# finalproject.net
KiCad netlist of a schematic drawn in Altium Designer
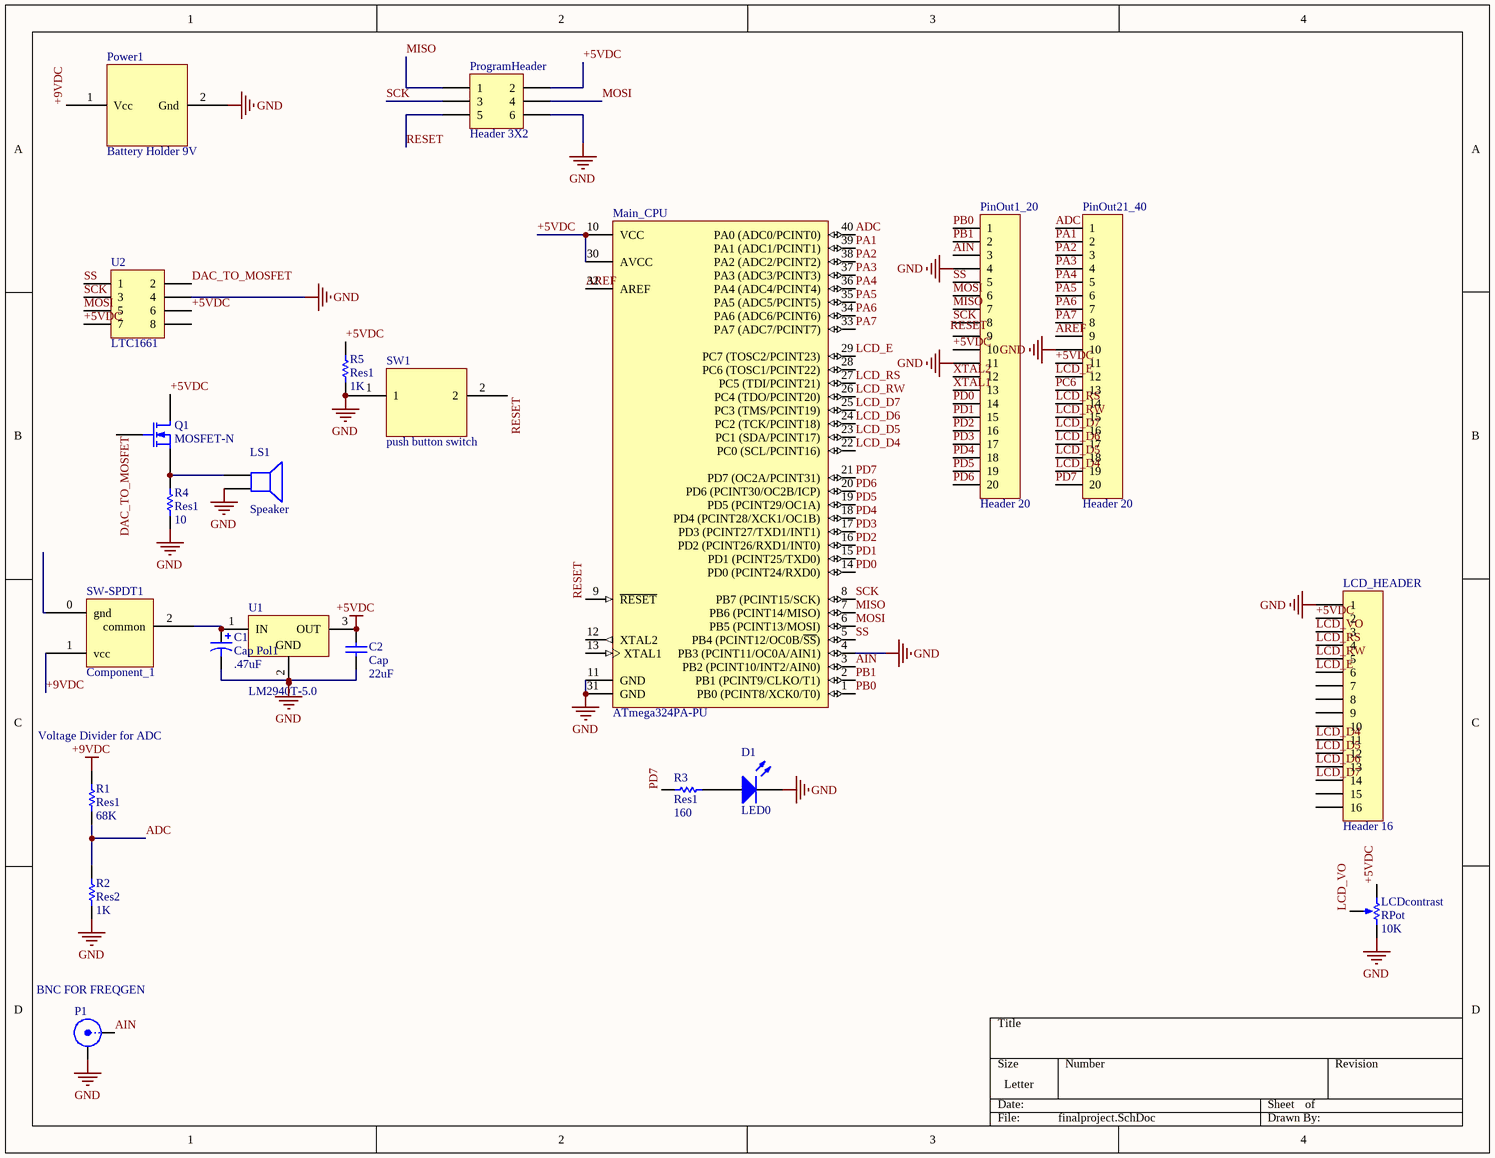
[diagram p0: finalproject.SchDoc]

(export (version "E")
  (design (tool "Eeschema 10.0.6"))
  (components
    (comp (ref "C1")
      (value "Cap Pol1")
      (footprint "HDR1X2")
      (description "Polarized Capacitor (Radial)")
      (fields (field (name "ALTIUM_VALUE") ".47uF") (field (name "PUBLISHER") "Altium Limited"))
      (libsource (lib "Miscellaneous Devices") (part "Cap Pol1"))
    )
    (comp (ref "C2")
      (value "Cap")
      (footprint "Vishay Sprague Tantalum Axial-Lead Capacitor:CSR13-D")
      (description "Capacitor")
      (fields (field (name "ALTIUM_VALUE") "22uF") (field (name "PUBLISHER") "Altium Limited"))
      (libsource (lib "Miscellaneous Devices") (part "Cap"))
    )
    (comp (ref "D1")
      (value "LED0")
      (footprint "HDR1X2")
      (description "Typical INFRARED GaAs LED")
      (fields (field (name "PUBLISHER") "Altium Limited"))
      (libsource (lib "Miscellaneous Devices") (part "LED0"))
    )
    (comp (ref "LCDcontrast")
      (value "RPot")
      (footprint "VR5")
      (description "Potentiometer")
      (fields (field (name "ALTIUM_VALUE") "10K") (field (name "PUBLISHER") "Altium Limited"))
      (libsource (lib "Miscellaneous Devices") (part "RPot"))
    )
    (comp (ref "LCD_HEADER")
      (value "Header 16")
      (footprint "HDR1X16")
      (description "Header, 16-Pin")
      (fields (field (name "PUBLISHER") "Altium Limited"))
      (libsource (lib "Miscellaneous Connectors") (part "Header 16"))
    )
    (comp (ref "LS1")
      (value "Speaker")
      (footprint "PIN2")
      (description "Loudspeaker")
      (fields (field (name "PUBLISHER") "Altium Limited"))
      (libsource (lib "Miscellaneous Devices") (part "Speaker"))
    )
    (comp (ref "Main_CPU")
      (value "ATmega324PA-PU")
      (footprint "40P6")
      (fields (field (name "PUBLISHER") "Altium Limited"))
      (libsource (lib "Atmel Microcontroller 8-Bit megaAVR") (part "ATmega324PA-PU"))
    )
    (comp (ref "P1")
      (value "BNC FOR FREQGEN")
      (footprint "BNC_RA CON")
      (description "BNC Elbow Connector")
      (fields (field (name "PUBLISHER") "Altium Limited"))
      (libsource (lib "Miscellaneous Connectors") (part "BNC"))
    )
    (comp (ref "PinOut1_20")
      (value "Header 20")
      (footprint "HDR1X20")
      (description "Header, 20-Pin")
      (fields (field (name "PUBLISHER") "Altium Limited"))
      (libsource (lib "Miscellaneous Connectors") (part "Header 20"))
    )
    (comp (ref "PinOut21_40")
      (value "Header 20")
      (footprint "HDR1X20")
      (description "Header, 20-Pin")
      (fields (field (name "PUBLISHER") "Altium Limited"))
      (libsource (lib "Miscellaneous Connectors") (part "Header 20"))
    )
    (comp (ref "Power1")
      (value "Battery Holder 9V")
      (footprint "PCBComponent_1 - duplicate")
      (libsource (lib "JDlibs") (part "Battery Holder 9V"))
    )
    (comp (ref "ProgramHeader")
      (value "Header 3X2")
      (footprint "HDR2X3")
      (description "Header, 3-Pin, Dual row")
      (fields (field (name "PUBLISHER") "Altium Limited"))
      (libsource (lib "Miscellaneous Connectors") (part "Header 3X2"))
    )
    (comp (ref "Q1")
      (value "MOSFET-N")
      (footprint "HDR1X3")
      (description "N-Channel MOSFET")
      (fields (field (name "PUBLISHER") "Altium Limited"))
      (libsource (lib "Miscellaneous Devices") (part "MOSFET-N"))
    )
    (comp (ref "R1")
      (value "Res1")
      (footprint "AXIAL-0.3")
      (description "Resistor")
      (fields (field (name "ALTIUM_VALUE") "68K") (field (name "PUBLISHER") "Altium Limited"))
      (libsource (lib "Miscellaneous Devices") (part "Res1"))
    )
    (comp (ref "R2")
      (value "Res2")
      (footprint "AXIAL-0.3")
      (description "Resistor")
      (fields (field (name "ALTIUM_VALUE") "1K") (field (name "PUBLISHER") "Altium Limited"))
      (libsource (lib "Miscellaneous Devices") (part "Res1"))
    )
    (comp (ref "R3")
      (value "Res1")
      (footprint "AXIAL-0.3")
      (description "Resistor")
      (fields (field (name "ALTIUM_VALUE") "160") (field (name "PUBLISHER") "Altium Limited"))
      (libsource (lib "Miscellaneous Devices") (part "Res1"))
    )
    (comp (ref "R4")
      (value "Res1")
      (footprint "AXIAL-0.3")
      (description "Resistor")
      (fields (field (name "ALTIUM_VALUE") "10") (field (name "PUBLISHER") "Altium Limited"))
      (libsource (lib "Miscellaneous Devices") (part "Res1"))
    )
    (comp (ref "R5")
      (value "Res1")
      (footprint "AXIAL-0.3")
      (description "Resistor")
      (fields (field (name "ALTIUM_VALUE") "1K") (field (name "PUBLISHER") "Altium Limited"))
      (libsource (lib "Miscellaneous Devices") (part "Res1"))
    )
    (comp (ref "SW-SPDT1")
      (value "Component_1")
      (footprint "PCBComponent_1")
      (libsource (lib "JDlibs") (part "Component_1"))
    )
    (comp (ref "SW1")
      (value "push button switch")
      (footprint "SW-PUSH-4")
      (libsource (lib "JDlibs") (part "SW-PUSH"))
    )
    (comp (ref "U1")
      (value "LM2940T-5.0")
      (footprint "T03B")
      (description "1A Low Dropout Regulator, 3-pin TO-220")
      (fields
        (field (name "MANUFACTURER") "National Semiconductor")
        (field (name "PUBLISHER") "Altium Limited")
      )
      (libsource (lib "NSC LDO") (part "LM2940T-5.0"))
    )
    (comp (ref "U2")
      (value "LTC1661")
      (footprint "DIP-8")
      (description "Header, 4-Pin, Dual row")
      (fields (field (name "PUBLISHER") "Altium Limited"))
      (libsource (lib "Miscellaneous Connectors") (part "Header 4X2"))
    )
  )
  (nets
    (net (code "1") (name "+5VDC") (class "Default")
      (node (ref "C2") (pin "2") (pinfunction "2_2") (pintype "passive"))
      (node (ref "LCD_HEADER") (pin "2") (pinfunction "2_2") (pintype "passive"))
      (node (ref "LCDcontrast") (pin "1") (pinfunction "TOP_1") (pintype "passive"))
      (node (ref "Main_CPU") (pin "10") (pinfunction "VCC_10") (pintype "power_in"))
      (node (ref "Main_CPU") (pin "30") (pinfunction "AVCC_30") (pintype "power_in"))
      (node (ref "PinOut1_20") (pin "10") (pinfunction "10_10") (pintype "passive"))
      (node (ref "PinOut21_40") (pin "11") (pinfunction "11_11") (pintype "passive"))
      (node (ref "ProgramHeader") (pin "2") (pinfunction "2_2") (pintype "passive"))
      (node (ref "Q1") (pin "1") (pinfunction "D_1") (pintype "passive"))
      (node (ref "R5") (pin "2") (pinfunction "2_2") (pintype "passive"))
      (node (ref "U1") (pin "3") (pinfunction "OUT_3") (pintype "power_in"))
      (node (ref "U2") (pin "6") (pinfunction "6_6") (pintype "passive"))
      (node (ref "U2") (pin "7") (pinfunction "7_7") (pintype "passive"))
    )
    (net (code "2") (name "+9VDC") (class "Default")
      (node (ref "Power1") (pin "1") (pinfunction "Vcc_1") (pintype "passive"))
      (node (ref "R1") (pin "2") (pinfunction "2_2") (pintype "passive"))
      (node (ref "SW-SPDT1") (pin "1") (pinfunction "vcc_1") (pintype "passive"))
    )
    (net (code "3") (name "/ADC") (class "Default")
      (node (ref "Main_CPU") (pin "40") (pinfunction "PA0_(ADC0/PCINT0)_40") (pintype "bidirectional"))
      (node (ref "PinOut21_40") (pin "1") (pinfunction "1_1") (pintype "passive"))
      (node (ref "R1") (pin "1") (pinfunction "1_1") (pintype "passive"))
      (node (ref "R2") (pin "2") (pinfunction "2_2") (pintype "passive"))
    )
    (net (code "4") (name "/AIN") (class "Default")
      (node (ref "Main_CPU") (pin "3") (pinfunction "PB2_(PCINT10/INT2/AIN0)_3") (pintype "bidirectional"))
      (node (ref "P1") (pin "1") (pinfunction "X_1") (pintype "passive"))
      (node (ref "PinOut1_20") (pin "3") (pinfunction "3_3") (pintype "passive"))
    )
    (net (code "5") (name "/AREF") (class "Default")
      (node (ref "Main_CPU") (pin "32") (pinfunction "AREF_32") (pintype "power_in"))
      (node (ref "PinOut21_40") (pin "9") (pinfunction "9_9") (pintype "passive"))
    )
    (net (code "6") (name "/DAC_TO_MOSFET") (class "Default")
      (node (ref "Q1") (pin "2") (pinfunction "G_2") (pintype "passive"))
      (node (ref "U2") (pin "2") (pinfunction "2_2") (pintype "passive"))
    )
    (net (code "7") (name "/LCD_D4") (class "Default")
      (node (ref "LCD_HEADER") (pin "11") (pinfunction "11_11") (pintype "passive"))
      (node (ref "Main_CPU") (pin "22") (pinfunction "PC0_(SCL/PCINT16)_22") (pintype "bidirectional"))
      (node (ref "PinOut21_40") (pin "19") (pinfunction "19_19") (pintype "passive"))
    )
    (net (code "8") (name "/LCD_D5") (class "Default")
      (node (ref "LCD_HEADER") (pin "12") (pinfunction "12_12") (pintype "passive"))
      (node (ref "Main_CPU") (pin "23") (pinfunction "PC1_(SDA/PCINT17)_23") (pintype "bidirectional"))
      (node (ref "PinOut21_40") (pin "18") (pinfunction "18_18") (pintype "passive"))
    )
    (net (code "9") (name "/LCD_D6") (class "Default")
      (node (ref "LCD_HEADER") (pin "13") (pinfunction "13_13") (pintype "passive"))
      (node (ref "Main_CPU") (pin "24") (pinfunction "PC2_(TCK/PCINT18)_24") (pintype "bidirectional"))
      (node (ref "PinOut21_40") (pin "17") (pinfunction "17_17") (pintype "passive"))
    )
    (net (code "10") (name "/LCD_D7") (class "Default")
      (node (ref "LCD_HEADER") (pin "14") (pinfunction "14_14") (pintype "passive"))
      (node (ref "Main_CPU") (pin "25") (pinfunction "PC3_(TMS/PCINT19)_25") (pintype "bidirectional"))
      (node (ref "PinOut21_40") (pin "16") (pinfunction "16_16") (pintype "passive"))
    )
    (net (code "11") (name "/LCD_E") (class "Default")
      (node (ref "LCD_HEADER") (pin "6") (pinfunction "6_6") (pintype "passive"))
      (node (ref "Main_CPU") (pin "29") (pinfunction "PC7_(TOSC2/PCINT23)_29") (pintype "bidirectional"))
      (node (ref "PinOut21_40") (pin "12") (pinfunction "12_12") (pintype "passive"))
    )
    (net (code "12") (name "/LCD_RS") (class "Default")
      (node (ref "LCD_HEADER") (pin "4") (pinfunction "4_4") (pintype "passive"))
      (node (ref "Main_CPU") (pin "27") (pinfunction "PC5_(TDI/PCINT21)_27") (pintype "bidirectional"))
      (node (ref "PinOut21_40") (pin "14") (pinfunction "14_14") (pintype "passive"))
    )
    (net (code "13") (name "/LCD_RW") (class "Default")
      (node (ref "LCD_HEADER") (pin "5") (pinfunction "5_5") (pintype "passive"))
      (node (ref "Main_CPU") (pin "26") (pinfunction "PC4_(TDO/PCINT20)_26") (pintype "bidirectional"))
      (node (ref "PinOut21_40") (pin "15") (pinfunction "15_15") (pintype "passive"))
    )
    (net (code "14") (name "/LCD_VO") (class "Default")
      (node (ref "LCD_HEADER") (pin "3") (pinfunction "3_3") (pintype "passive"))
      (node (ref "LCDcontrast") (pin "3") (pinfunction "TAP_3") (pintype "passive"))
    )
    (net (code "15") (name "/MISO") (class "Default")
      (node (ref "Main_CPU") (pin "7") (pinfunction "PB6_(PCINT14/MISO)_7") (pintype "bidirectional"))
      (node (ref "PinOut1_20") (pin "7") (pinfunction "7_7") (pintype "passive"))
      (node (ref "ProgramHeader") (pin "1") (pinfunction "1_1") (pintype "passive"))
    )
    (net (code "16") (name "/MOSI") (class "Default")
      (node (ref "Main_CPU") (pin "6") (pinfunction "PB5_(PCINT13/MOSI)_6") (pintype "bidirectional"))
      (node (ref "PinOut1_20") (pin "6") (pinfunction "6_6") (pintype "passive"))
      (node (ref "ProgramHeader") (pin "4") (pinfunction "4_4") (pintype "passive"))
      (node (ref "U2") (pin "5") (pinfunction "5_5") (pintype "passive"))
    )
    (net (code "17") (name "/PA1") (class "Default")
      (node (ref "Main_CPU") (pin "39") (pinfunction "PA1_(ADC1/PCINT1)_39") (pintype "bidirectional"))
      (node (ref "PinOut21_40") (pin "2") (pinfunction "2_2") (pintype "passive"))
    )
    (net (code "18") (name "/PA2") (class "Default")
      (node (ref "Main_CPU") (pin "38") (pinfunction "PA2_(ADC2/PCINT2)_38") (pintype "bidirectional"))
      (node (ref "PinOut21_40") (pin "3") (pinfunction "3_3") (pintype "passive"))
    )
    (net (code "19") (name "/PA3") (class "Default")
      (node (ref "Main_CPU") (pin "37") (pinfunction "PA3_(ADC3/PCINT3)_37") (pintype "bidirectional"))
      (node (ref "PinOut21_40") (pin "4") (pinfunction "4_4") (pintype "passive"))
    )
    (net (code "20") (name "/PA4") (class "Default")
      (node (ref "Main_CPU") (pin "36") (pinfunction "PA4_(ADC4/PCINT4)_36") (pintype "bidirectional"))
      (node (ref "PinOut21_40") (pin "5") (pinfunction "5_5") (pintype "passive"))
    )
    (net (code "21") (name "/PA5") (class "Default")
      (node (ref "Main_CPU") (pin "35") (pinfunction "PA5_(ADC5/PCINT5)_35") (pintype "bidirectional"))
      (node (ref "PinOut21_40") (pin "6") (pinfunction "6_6") (pintype "passive"))
    )
    (net (code "22") (name "/PA6") (class "Default")
      (node (ref "Main_CPU") (pin "34") (pinfunction "PA6_(ADC6/PCINT6)_34") (pintype "bidirectional"))
      (node (ref "PinOut21_40") (pin "7") (pinfunction "7_7") (pintype "passive"))
    )
    (net (code "23") (name "/PA7") (class "Default")
      (node (ref "Main_CPU") (pin "33") (pinfunction "PA7_(ADC7/PCINT7)_33") (pintype "bidirectional"))
      (node (ref "PinOut21_40") (pin "8") (pinfunction "8_8") (pintype "passive"))
    )
    (net (code "24") (name "/PB0") (class "Default")
      (node (ref "Main_CPU") (pin "1") (pinfunction "PB0_(PCINT8/XCK0/T0)_1") (pintype "bidirectional"))
      (node (ref "PinOut1_20") (pin "1") (pinfunction "1_1") (pintype "passive"))
    )
    (net (code "25") (name "/PB1") (class "Default")
      (node (ref "Main_CPU") (pin "2") (pinfunction "PB1_(PCINT9/CLKO/T1)_2") (pintype "bidirectional"))
      (node (ref "PinOut1_20") (pin "2") (pinfunction "2_2") (pintype "passive"))
    )
    (net (code "26") (name "/PC6") (class "Default")
      (node (ref "PinOut21_40") (pin "13") (pinfunction "13_13") (pintype "passive"))
    )
    (net (code "27") (name "/PD0") (class "Default")
      (node (ref "Main_CPU") (pin "14") (pinfunction "PD0_(PCINT24/RXD0)_14") (pintype "bidirectional"))
      (node (ref "PinOut1_20") (pin "14") (pinfunction "14_14") (pintype "passive"))
    )
    (net (code "28") (name "/PD1") (class "Default")
      (node (ref "Main_CPU") (pin "15") (pinfunction "PD1_(PCINT25/TXD0)_15") (pintype "bidirectional"))
      (node (ref "PinOut1_20") (pin "15") (pinfunction "15_15") (pintype "passive"))
    )
    (net (code "29") (name "/PD2") (class "Default")
      (node (ref "Main_CPU") (pin "16") (pinfunction "PD2_(PCINT26/RXD1/INT0)_16") (pintype "bidirectional"))
      (node (ref "PinOut1_20") (pin "16") (pinfunction "16_16") (pintype "passive"))
    )
    (net (code "30") (name "/PD3") (class "Default")
      (node (ref "Main_CPU") (pin "17") (pinfunction "PD3_(PCINT27/TXD1/INT1)_17") (pintype "bidirectional"))
      (node (ref "PinOut1_20") (pin "17") (pinfunction "17_17") (pintype "passive"))
    )
    (net (code "31") (name "/PD4") (class "Default")
      (node (ref "Main_CPU") (pin "18") (pinfunction "PD4_(PCINT28/XCK1/OC1B)_18") (pintype "bidirectional"))
      (node (ref "PinOut1_20") (pin "18") (pinfunction "18_18") (pintype "passive"))
    )
    (net (code "32") (name "/PD5") (class "Default")
      (node (ref "Main_CPU") (pin "19") (pinfunction "PD5_(PCINT29/OC1A)_19") (pintype "bidirectional"))
      (node (ref "PinOut1_20") (pin "19") (pinfunction "19_19") (pintype "passive"))
    )
    (net (code "33") (name "/PD6") (class "Default")
      (node (ref "Main_CPU") (pin "20") (pinfunction "PD6_(PCINT30/OC2B/ICP)_20") (pintype "bidirectional"))
      (node (ref "PinOut1_20") (pin "20") (pinfunction "20_20") (pintype "passive"))
    )
    (net (code "34") (name "/PD7") (class "Default")
      (node (ref "Main_CPU") (pin "21") (pinfunction "PD7_(OC2A/PCINT31)_21") (pintype "bidirectional"))
      (node (ref "PinOut21_40") (pin "20") (pinfunction "20_20") (pintype "passive"))
      (node (ref "R3") (pin "1") (pinfunction "1_1") (pintype "passive"))
    )
    (net (code "35") (name "/RESET") (class "Default")
      (node (ref "Main_CPU") (pin "9") (pinfunction "~{RESET}_9") (pintype "input"))
      (node (ref "ProgramHeader") (pin "5") (pinfunction "5_5") (pintype "passive"))
      (node (ref "SW1") (pin "2") (pinfunction "2_2") (pintype "passive"))
    )
    (net (code "36") (name "/SCK") (class "Default")
      (node (ref "Main_CPU") (pin "8") (pinfunction "PB7_(PCINT15/SCK)_8") (pintype "bidirectional"))
      (node (ref "PinOut1_20") (pin "8") (pinfunction "8_8") (pintype "passive"))
      (node (ref "ProgramHeader") (pin "3") (pinfunction "3_3") (pintype "passive"))
      (node (ref "U2") (pin "3") (pinfunction "3_3") (pintype "passive"))
    )
    (net (code "37") (name "/SS") (class "Default")
      (node (ref "Main_CPU") (pin "5") (pinfunction "PB4_(PCINT12/OC0B/~{SS})_5") (pintype "bidirectional"))
      (node (ref "PinOut1_20") (pin "5") (pinfunction "5_5") (pintype "passive"))
      (node (ref "U2") (pin "1") (pinfunction "1_1") (pintype "passive"))
    )
    (net (code "38") (name "/XTAL1") (class "Default")
      (node (ref "PinOut1_20") (pin "13") (pinfunction "13_13") (pintype "passive"))
    )
    (net (code "39") (name "/XTAL2") (class "Default")
      (node (ref "PinOut1_20") (pin "12") (pinfunction "12_12") (pintype "passive"))
    )
    (net (code "40") (name "GND") (class "Default")
      (node (ref "C1") (pin "2") (pinfunction "2_2") (pintype "passive"))
      (node (ref "C2") (pin "1") (pinfunction "1_1") (pintype "passive"))
      (node (ref "D1") (pin "2") (pinfunction "K_2") (pintype "passive"))
      (node (ref "LCD_HEADER") (pin "1") (pinfunction "1_1") (pintype "passive"))
      (node (ref "LCDcontrast") (pin "2") (pinfunction "BOT_2") (pintype "passive"))
      (node (ref "LS1") (pin "2") (pinfunction "2_2") (pintype "passive"))
      (node (ref "Main_CPU") (pin "11") (pinfunction "GND_11") (pintype "power_in"))
      (node (ref "Main_CPU") (pin "31") (pinfunction "GND_31") (pintype "power_in"))
      (node (ref "Main_CPU") (pin "4") (pinfunction "PB3_(PCINT11/OC0A/AIN1)_4") (pintype "bidirectional"))
      (node (ref "P1") (pin "2") (pinfunction "Y_2") (pintype "passive"))
      (node (ref "PinOut1_20") (pin "11") (pinfunction "11_11") (pintype "passive"))
      (node (ref "PinOut1_20") (pin "4") (pinfunction "4_4") (pintype "passive"))
      (node (ref "PinOut21_40") (pin "10") (pinfunction "10_10") (pintype "passive"))
      (node (ref "Power1") (pin "2") (pinfunction "Gnd_2") (pintype "passive"))
      (node (ref "ProgramHeader") (pin "6") (pinfunction "6_6") (pintype "passive"))
      (node (ref "R2") (pin "1") (pinfunction "1_1") (pintype "passive"))
      (node (ref "R4") (pin "1") (pinfunction "1_1") (pintype "passive"))
      (node (ref "R5") (pin "1") (pinfunction "1_1") (pintype "passive"))
      (node (ref "SW1") (pin "1") (pinfunction "1_1") (pintype "passive"))
      (node (ref "U1") (pin "2") (pinfunction "GND_2") (pintype "power_in"))
      (node (ref "U2") (pin "4") (pinfunction "4_4") (pintype "passive"))
    )
    (net (code "41") (name "Net-(D1-A)") (class "Default")
      (node (ref "D1") (pin "1") (pinfunction "A_1") (pintype "passive"))
      (node (ref "R3") (pin "2") (pinfunction "2_2") (pintype "passive"))
    )
    (net (code "42") (name "Net-(Q1-S)") (class "Default")
      (node (ref "LS1") (pin "1") (pinfunction "1_1") (pintype "passive"))
      (node (ref "Q1") (pin "3") (pinfunction "S_3") (pintype "passive"))
      (node (ref "R4") (pin "2") (pinfunction "2_2") (pintype "passive"))
    )
    (net (code "43") (name "Net-(SW-SPDT1-common)") (class "Default")
      (node (ref "C1") (pin "1") (pinfunction "1_1") (pintype "passive"))
      (node (ref "SW-SPDT1") (pin "2") (pinfunction "common_2") (pintype "passive"))
      (node (ref "U1") (pin "1") (pinfunction "IN_1") (pintype "power_in"))
    )
    (net (code "44") (name "unconnected-(LCD_HEADER-Pad7)") (class "Default")
      (node (ref "LCD_HEADER") (pin "7") (pinfunction "7_7") (pintype "passive"))
    )
    (net (code "45") (name "unconnected-(LCD_HEADER-Pad8)") (class "Default")
      (node (ref "LCD_HEADER") (pin "8") (pinfunction "8_8") (pintype "passive"))
    )
    (net (code "46") (name "unconnected-(LCD_HEADER-Pad9)") (class "Default")
      (node (ref "LCD_HEADER") (pin "9") (pinfunction "9_9") (pintype "passive"))
    )
    (net (code "47") (name "unconnected-(LCD_HEADER-Pad10)") (class "Default")
      (node (ref "LCD_HEADER") (pin "10") (pinfunction "10_10") (pintype "passive"))
    )
    (net (code "48") (name "unconnected-(LCD_HEADER-Pad15)") (class "Default")
      (node (ref "LCD_HEADER") (pin "15") (pinfunction "15_15") (pintype "passive"))
    )
    (net (code "49") (name "unconnected-(LCD_HEADER-Pad16)") (class "Default")
      (node (ref "LCD_HEADER") (pin "16") (pinfunction "16_16") (pintype "passive"))
    )
    (net (code "50") (name "unconnected-(Main_CPU-PC6_(TOSC1{slash}PCINT22)-Pad28)") (class "Default")
      (node (ref "Main_CPU") (pin "28") (pinfunction "PC6_(TOSC1/PCINT22)_28") (pintype "bidirectional"))
    )
    (net (code "51") (name "unconnected-(Main_CPU-XTAL1-Pad13)") (class "Default")
      (node (ref "Main_CPU") (pin "13") (pinfunction "XTAL1_13") (pintype "input"))
    )
    (net (code "52") (name "unconnected-(Main_CPU-XTAL2-Pad12)") (class "Default")
      (node (ref "Main_CPU") (pin "12") (pinfunction "XTAL2_12") (pintype "output"))
    )
    (net (code "53") (name "unconnected-(PinOut1_20-Pad9)") (class "Default")
      (node (ref "PinOut1_20") (pin "9") (pinfunction "9_9") (pintype "passive"))
    )
    (net (code "54") (name "unconnected-(Power1-NC-Pad3)") (class "Default")
      (node (ref "Power1") (pin "3") (pinfunction "NC_3") (pintype "passive"))
    )
    (net (code "55") (name "unconnected-(SW-SPDT1-NC-Pad3)") (class "Default")
      (node (ref "SW-SPDT1") (pin "3") (pinfunction "NC_3") (pintype "passive"))
    )
    (net (code "56") (name "unconnected-(SW-SPDT1-gnd-Pad0)") (class "Default")
      (node (ref "SW-SPDT1") (pin "0") (pinfunction "gnd_0") (pintype "passive"))
    )
    (net (code "57") (name "unconnected-(U2-Pad8)") (class "Default")
      (node (ref "U2") (pin "8") (pinfunction "8_8") (pintype "passive"))
    )
  )
)
